# md_ver10_4.net
KiCad netlist of a schematic drawn in EAGLE
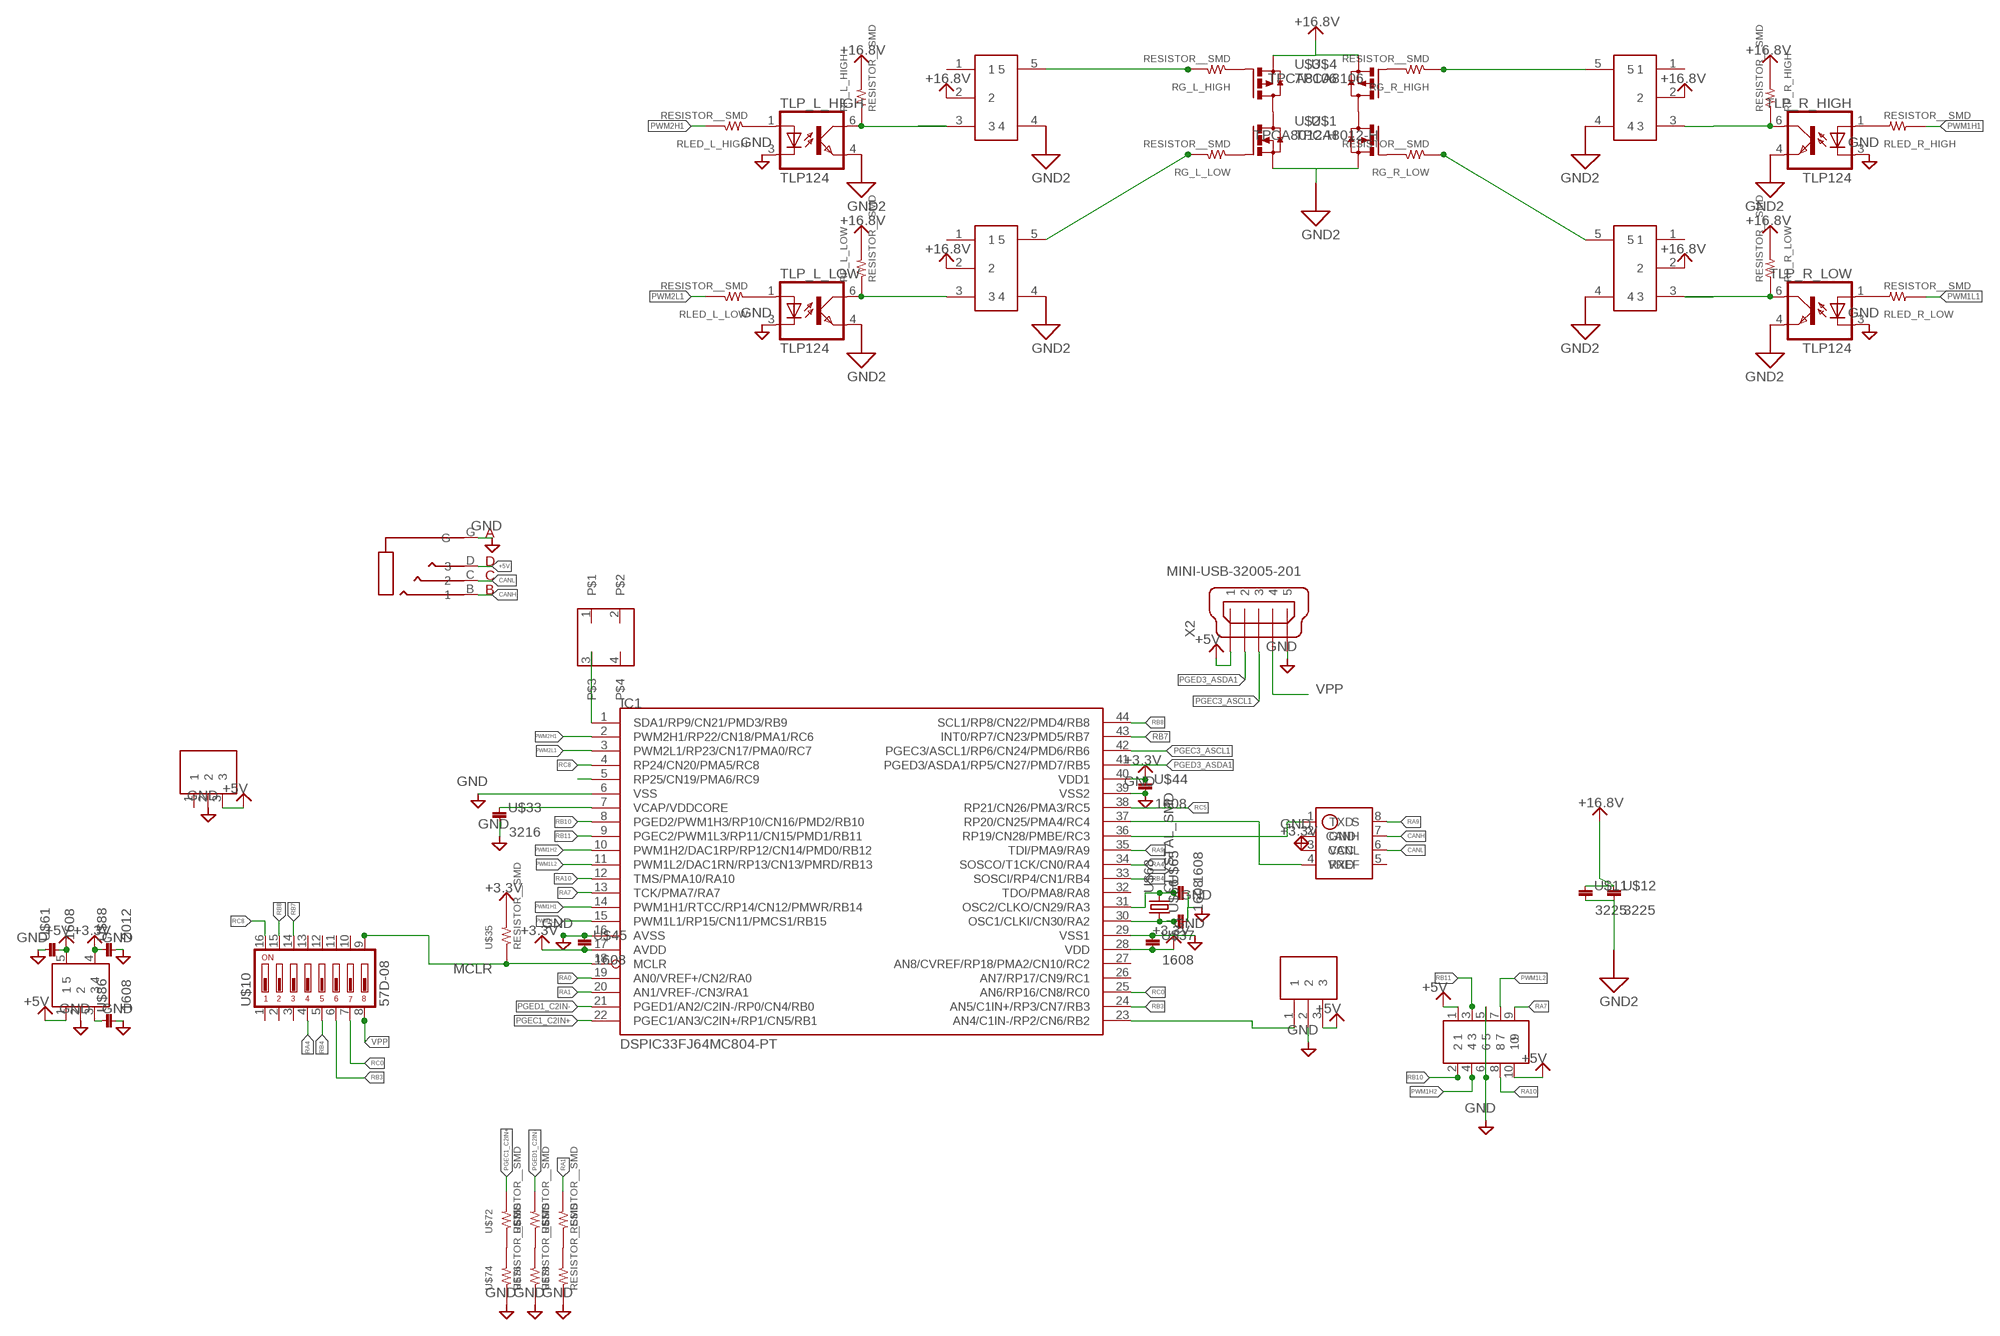
[diagram p0: schematic, sheet 1]

(export (version "E")
  (design (tool "Eeschema 10.0.6"))
  (components
    (comp (ref "IC1")
      (value "DSPIC33FJ64MC804-PT")
      (footprint "eagle-import:TQFP44")
      (libsource (lib "eagle-import") (part "DSPIC33FJ64MC804-PT"))
    )
    (comp (ref "IC_L_HIGH")
      (value "MCP1415")
      (footprint "eagle-import:SOT23-5L")
      (libsource (lib "eagle-import") (part "MCP1415"))
    )
    (comp (ref "IC_L_LOW")
      (value "MCP1415")
      (footprint "eagle-import:SOT23-5L")
      (libsource (lib "eagle-import") (part "MCP1415"))
    )
    (comp (ref "IC_R_HIGH")
      (value "MCP1415")
      (footprint "eagle-import:SOT23-5L")
      (libsource (lib "eagle-import") (part "MCP1415"))
    )
    (comp (ref "IC_R_LOW")
      (value "MCP1415")
      (footprint "eagle-import:SOT23-5L")
      (libsource (lib "eagle-import") (part "MCP1415"))
    )
    (comp (ref "RG_L_HIGH")
      (value "RESISTOR__SMD")
      (footprint "eagle-import:1608")
      (libsource (lib "eagle-import") (part "RESISTOR__SMD"))
    )
    (comp (ref "RG_L_LOW")
      (value "RESISTOR__SMD")
      (footprint "eagle-import:1608")
      (libsource (lib "eagle-import") (part "RESISTOR__SMD"))
    )
    (comp (ref "RG_R_HIGH")
      (value "RESISTOR__SMD")
      (footprint "eagle-import:1608")
      (libsource (lib "eagle-import") (part "RESISTOR__SMD"))
    )
    (comp (ref "RG_R_LOW")
      (value "RESISTOR__SMD")
      (footprint "eagle-import:1608")
      (libsource (lib "eagle-import") (part "RESISTOR__SMD"))
    )
    (comp (ref "RLED_L_HIGH")
      (value "RESISTOR__SMD")
      (footprint "eagle-import:1608")
      (libsource (lib "eagle-import") (part "RESISTOR__SMD"))
    )
    (comp (ref "RLED_L_LOW")
      (value "RESISTOR__SMD")
      (footprint "eagle-import:1608")
      (libsource (lib "eagle-import") (part "RESISTOR__SMD"))
    )
    (comp (ref "RLED_R_HIGH")
      (value "RESISTOR__SMD")
      (footprint "eagle-import:1608")
      (libsource (lib "eagle-import") (part "RESISTOR__SMD"))
    )
    (comp (ref "RLED_R_LOW")
      (value "RESISTOR__SMD")
      (footprint "eagle-import:1608")
      (libsource (lib "eagle-import") (part "RESISTOR__SMD"))
    )
    (comp (ref "RP_L_HIGH")
      (value "RESISTOR__SMD")
      (footprint "eagle-import:1608")
      (libsource (lib "eagle-import") (part "RESISTOR__SMD"))
    )
    (comp (ref "RP_L_LOW")
      (value "RESISTOR__SMD")
      (footprint "eagle-import:1608")
      (libsource (lib "eagle-import") (part "RESISTOR__SMD"))
    )
    (comp (ref "RP_R_HIGH")
      (value "RESISTOR__SMD")
      (footprint "eagle-import:1608")
      (libsource (lib "eagle-import") (part "RESISTOR__SMD"))
    )
    (comp (ref "RP_R_LOW")
      (value "RESISTOR__SMD")
      (footprint "eagle-import:1608")
      (libsource (lib "eagle-import") (part "RESISTOR__SMD"))
    )
    (comp (ref "TLP_L_HIGH")
      (value "TLP124")
      (footprint "eagle-import:11−4C1")
      (libsource (lib "eagle-import") (part "TLP124"))
    )
    (comp (ref "TLP_L_LOW")
      (value "TLP124")
      (footprint "eagle-import:11−4C1")
      (libsource (lib "eagle-import") (part "TLP124"))
    )
    (comp (ref "TLP_R_HIGH")
      (value "TLP124")
      (footprint "eagle-import:11−4C1")
      (libsource (lib "eagle-import") (part "TLP124"))
    )
    (comp (ref "TLP_R_LOW")
      (value "TLP124")
      (footprint "eagle-import:11−4C1")
      (libsource (lib "eagle-import") (part "TLP124"))
    )
    (comp (ref "U$1")
      (value "TPCA8012-H")
      (footprint "eagle-import:2-5Q1A")
      (libsource (lib "eagle-import") (part "TPCA8012-H"))
    )
    (comp (ref "U$2")
      (value "TPCA8012-H")
      (footprint "eagle-import:2-5Q1A")
      (libsource (lib "eagle-import") (part "TPCA8012-H"))
    )
    (comp (ref "U$3")
      (value "TPCA8106")
      (footprint "eagle-import:2-5Q1A")
      (libsource (lib "eagle-import") (part "TPCA8106"))
    )
    (comp (ref "U$4")
      (value "TPCA8106")
      (footprint "eagle-import:2-5Q1A")
      (libsource (lib "eagle-import") (part "TPCA8106"))
    )
    (comp (ref "U$7")
      (value "ＰＬ－ＩＲＭ")
      (footprint "eagle-import:ＰＬ－ＩＲＭ")
      (libsource (lib "eagle-import") (part "ＰＬ－ＩＲＭ"))
    )
    (comp (ref "U$8")
      (value "Ｒ－７８Ｅ５．０")
      (footprint "eagle-import:Ｒ－７８Ｅ５．０")
      (libsource (lib "eagle-import") (part "Ｒ－７８Ｅ５．０"))
    )
    (comp (ref "U$9")
      (value "TAR5SB")
      (footprint "eagle-import:SSOP5-P-0.95")
      (libsource (lib "eagle-import") (part "TAR5SB"))
    )
    (comp (ref "U$10")
      (value "57D-08")
      (footprint "eagle-import:57D")
      (libsource (lib "eagle-import") (part "57D-08"))
    )
    (comp (ref "U$11")
      (value "3225")
      (footprint "eagle-import:3225")
      (libsource (lib "eagle-import") (part "3225"))
    )
    (comp (ref "U$12")
      (value "3225")
      (footprint "eagle-import:3225")
      (libsource (lib "eagle-import") (part "3225"))
    )
    (comp (ref "U$15")
      (value "PIN_HEADER_52")
      (footprint "eagle-import:PIN_HEADER_5_2")
      (libsource (lib "eagle-import") (part "PIN_HEADER_52"))
    )
    (comp (ref "U$33")
      (value "3216")
      (footprint "eagle-import:3216")
      (libsource (lib "eagle-import") (part "3216"))
    )
    (comp (ref "U$35")
      (value "RESISTOR__SMD")
      (footprint "eagle-import:1608")
      (libsource (lib "eagle-import") (part "RESISTOR__SMD"))
    )
    (comp (ref "U$37")
      (value "1608")
      (footprint "eagle-import:1608")
      (libsource (lib "eagle-import") (part "1608"))
    )
    (comp (ref "U$44")
      (value "1608")
      (footprint "eagle-import:1608")
      (libsource (lib "eagle-import") (part "1608"))
    )
    (comp (ref "U$45")
      (value "1608")
      (footprint "eagle-import:1608")
      (libsource (lib "eagle-import") (part "1608"))
    )
    (comp (ref "U$61")
      (value "1608")
      (footprint "eagle-import:1608")
      (libsource (lib "eagle-import") (part "1608"))
    )
    (comp (ref "U$64")
      (value "AUDIO4")
      (footprint "eagle-import:AUDIO4_MJ")
      (libsource (lib "eagle-import") (part "AUDIO4"))
    )
    (comp (ref "U$65")
      (value "1608")
      (footprint "eagle-import:1608")
      (libsource (lib "eagle-import") (part "1608"))
    )
    (comp (ref "U$66")
      (value "1608")
      (footprint "eagle-import:1608")
      (libsource (lib "eagle-import") (part "1608"))
    )
    (comp (ref "U$68")
      (value "CLYSTAL_SMD")
      (footprint "eagle-import:CRYSTAL_SMD")
      (libsource (lib "eagle-import") (part "CLYSTAL_SMD"))
    )
    (comp (ref "U$69")
      (value "TACT")
      (footprint "eagle-import:TL1105")
      (libsource (lib "eagle-import") (part "TACT"))
    )
    (comp (ref "U$72")
      (value "RESISTOR__SMD")
      (footprint "eagle-import:1608")
      (libsource (lib "eagle-import") (part "RESISTOR__SMD"))
    )
    (comp (ref "U$74")
      (value "RESISTOR__SMD")
      (footprint "eagle-import:1608")
      (libsource (lib "eagle-import") (part "RESISTOR__SMD"))
    )
    (comp (ref "U$75")
      (value "RESISTOR__SMD")
      (footprint "eagle-import:1608")
      (libsource (lib "eagle-import") (part "RESISTOR__SMD"))
    )
    (comp (ref "U$76")
      (value "RESISTOR__SMD")
      (footprint "eagle-import:1608")
      (libsource (lib "eagle-import") (part "RESISTOR__SMD"))
    )
    (comp (ref "U$77")
      (value "RESISTOR__SMD")
      (footprint "eagle-import:1608")
      (libsource (lib "eagle-import") (part "RESISTOR__SMD"))
    )
    (comp (ref "U$78")
      (value "RESISTOR__SMD")
      (footprint "eagle-import:1608")
      (libsource (lib "eagle-import") (part "RESISTOR__SMD"))
    )
    (comp (ref "U$82")
      (value "SN65HVD1050")
      (footprint "eagle-import:SOIC8")
      (libsource (lib "eagle-import") (part "SN65HVD1050"))
    )
    (comp (ref "U$86")
      (value "1608")
      (footprint "eagle-import:1608")
      (libsource (lib "eagle-import") (part "1608"))
    )
    (comp (ref "U$88")
      (value "2012")
      (footprint "eagle-import:2012")
      (libsource (lib "eagle-import") (part "2012"))
    )
    (comp (ref "X2")
      (value "MINI-USB-32005-201")
      (footprint "eagle-import:32005-201")
      (libsource (lib "eagle-import") (part "MINI-USB-32005-201"))
    )
  )
  (nets
    (net (code "1") (name "+3.3V") (class "Default")
      (node (ref "IC1") (pin "17") (pinfunction "AVDD_17") (pintype "power_in"))
      (node (ref "IC1") (pin "28") (pinfunction "VDD_28") (pintype "power_in"))
      (node (ref "IC1") (pin "40") (pinfunction "VDD1_40") (pintype "power_in"))
      (node (ref "U$35") (pin "2") (pinfunction "P$2_2") (pintype "passive"))
      (node (ref "U$37") (pin "P$2") (pinfunction "2_P$2") (pintype "passive"))
      (node (ref "U$44") (pin "P$1") (pinfunction "1_P$1") (pintype "passive"))
      (node (ref "U$45") (pin "P$2") (pinfunction "2_P$2") (pintype "passive"))
      (node (ref "U$82") (pin "3") (pinfunction "VCC_3") (pintype "bidirectional"))
      (node (ref "U$88") (pin "1") (pinfunction "1_1") (pintype "passive"))
      (node (ref "U$9") (pin "4") (pinfunction "4_4") (pintype "bidirectional"))
    )
    (net (code "2") (name "+5V") (class "Default")
      (node (ref "U$15") (pin "1") (pinfunction "1_1") (pintype "bidirectional"))
      (node (ref "U$15") (pin "10") (pinfunction "10_10") (pintype "bidirectional"))
      (node (ref "U$61") (pin "P$2") (pinfunction "2_P$2") (pintype "passive"))
      (node (ref "U$64") (pin "D") (pinfunction "3_D") (pintype "bidirectional"))
      (node (ref "U$7") (pin "3") (pinfunction "3_3") (pintype "bidirectional"))
      (node (ref "U$8") (pin "3") (pinfunction "3_3") (pintype "bidirectional"))
      (node (ref "U$9") (pin "1") (pinfunction "1_1") (pintype "bidirectional"))
      (node (ref "U$9") (pin "5") (pinfunction "5_5") (pintype "bidirectional"))
      (node (ref "X2") (pin "1") (pinfunction "1_1") (pintype "passive"))
    )
    (net (code "3") (name "+16.8V") (class "Default")
      (node (ref "IC_L_HIGH") (pin "2") (pinfunction "2_2") (pintype "bidirectional"))
      (node (ref "IC_L_LOW") (pin "2") (pinfunction "2_2") (pintype "bidirectional"))
      (node (ref "IC_R_HIGH") (pin "2") (pinfunction "2_2") (pintype "bidirectional"))
      (node (ref "IC_R_LOW") (pin "2") (pinfunction "2_2") (pintype "bidirectional"))
      (node (ref "RP_L_HIGH") (pin "2") (pinfunction "P$2_2") (pintype "passive"))
      (node (ref "RP_L_LOW") (pin "2") (pinfunction "P$2_2") (pintype "passive"))
      (node (ref "RP_R_HIGH") (pin "2") (pinfunction "P$2_2") (pintype "passive"))
      (node (ref "RP_R_LOW") (pin "2") (pinfunction "P$2_2") (pintype "passive"))
      (node (ref "U$11") (pin "P$1") (pinfunction "1_P$1") (pintype "passive"))
      (node (ref "U$12") (pin "P$1") (pinfunction "1_P$1") (pintype "passive"))
      (node (ref "U$3") (pin "1") (pinfunction "S_1") (pintype "passive"))
      (node (ref "U$3") (pin "2") (pinfunction "S_2") (pintype "passive"))
      (node (ref "U$3") (pin "3") (pinfunction "S_3") (pintype "passive"))
      (node (ref "U$4") (pin "1") (pinfunction "S_1") (pintype "passive"))
      (node (ref "U$4") (pin "2") (pinfunction "S_2") (pintype "passive"))
      (node (ref "U$4") (pin "3") (pinfunction "S_3") (pintype "passive"))
    )
    (net (code "4") (name "/MCLR") (class "Default")
      (node (ref "IC1") (pin "18") (pinfunction "MCLR_18") (pintype "input"))
      (node (ref "U$10") (pin "9") (pinfunction "9_9") (pintype "passive"))
      (node (ref "U$35") (pin "1") (pinfunction "P$1_1") (pintype "passive"))
    )
    (net (code "5") (name "CANH") (class "Default")
      (node (ref "U$64") (pin "B") (pinfunction "1_B") (pintype "bidirectional"))
      (node (ref "U$82") (pin "7") (pinfunction "CANH_7") (pintype "bidirectional"))
    )
    (net (code "6") (name "CANL") (class "Default")
      (node (ref "U$64") (pin "C") (pinfunction "2_C") (pintype "bidirectional"))
      (node (ref "U$82") (pin "6") (pinfunction "CANL_6") (pintype "bidirectional"))
    )
    (net (code "7") (name "GND") (class "Default")
      (node (ref "IC1") (pin "16") (pinfunction "AVSS_16") (pintype "power_in"))
      (node (ref "IC1") (pin "29") (pinfunction "VSS1_29") (pintype "power_in"))
      (node (ref "IC1") (pin "39") (pinfunction "VSS2_39") (pintype "power_in"))
      (node (ref "IC1") (pin "6") (pinfunction "VSS_6") (pintype "power_in"))
      (node (ref "TLP_L_HIGH") (pin "3") (pinfunction "C_3") (pintype "passive"))
      (node (ref "TLP_L_LOW") (pin "3") (pinfunction "C_3") (pintype "passive"))
      (node (ref "TLP_R_HIGH") (pin "3") (pinfunction "C_3") (pintype "passive"))
      (node (ref "TLP_R_LOW") (pin "3") (pinfunction "C_3") (pintype "passive"))
      (node (ref "U$15") (pin "5") (pinfunction "5_5") (pintype "bidirectional"))
      (node (ref "U$15") (pin "6") (pinfunction "6_6") (pintype "bidirectional"))
      (node (ref "U$33") (pin "P$2") (pinfunction "2_P$2") (pintype "passive"))
      (node (ref "U$37") (pin "P$1") (pinfunction "1_P$1") (pintype "passive"))
      (node (ref "U$44") (pin "P$2") (pinfunction "2_P$2") (pintype "passive"))
      (node (ref "U$45") (pin "P$1") (pinfunction "1_P$1") (pintype "passive"))
      (node (ref "U$61") (pin "P$1") (pinfunction "1_P$1") (pintype "passive"))
      (node (ref "U$64") (pin "G") (pinfunction "G_G") (pintype "bidirectional"))
      (node (ref "U$65") (pin "P$2") (pinfunction "2_P$2") (pintype "passive"))
      (node (ref "U$66") (pin "P$2") (pinfunction "2_P$2") (pintype "passive"))
      (node (ref "U$7") (pin "2") (pinfunction "2_2") (pintype "bidirectional"))
      (node (ref "U$74") (pin "1") (pinfunction "P$1_1") (pintype "passive"))
      (node (ref "U$76") (pin "1") (pinfunction "P$1_1") (pintype "passive"))
      (node (ref "U$78") (pin "1") (pinfunction "P$1_1") (pintype "passive"))
      (node (ref "U$8") (pin "2") (pinfunction "2_2") (pintype "bidirectional"))
      (node (ref "U$82") (pin "2") (pinfunction "GND_2") (pintype "bidirectional"))
      (node (ref "U$86") (pin "P$2") (pinfunction "2_P$2") (pintype "passive"))
      (node (ref "U$88") (pin "2") (pinfunction "2_2") (pintype "passive"))
      (node (ref "U$9") (pin "2") (pinfunction "2_2") (pintype "bidirectional"))
      (node (ref "X2") (pin "5") (pinfunction "5_5") (pintype "passive"))
    )
    (net (code "8") (name "GND2") (class "Default")
      (node (ref "IC_L_HIGH") (pin "4") (pinfunction "4_4") (pintype "bidirectional"))
      (node (ref "IC_L_LOW") (pin "4") (pinfunction "4_4") (pintype "bidirectional"))
      (node (ref "IC_R_HIGH") (pin "4") (pinfunction "4_4") (pintype "bidirectional"))
      (node (ref "IC_R_LOW") (pin "4") (pinfunction "4_4") (pintype "bidirectional"))
      (node (ref "TLP_L_HIGH") (pin "4") (pinfunction "EMIT_4") (pintype "passive"))
      (node (ref "TLP_L_LOW") (pin "4") (pinfunction "EMIT_4") (pintype "passive"))
      (node (ref "TLP_R_HIGH") (pin "4") (pinfunction "EMIT_4") (pintype "passive"))
      (node (ref "TLP_R_LOW") (pin "4") (pinfunction "EMIT_4") (pintype "passive"))
      (node (ref "U$1") (pin "1") (pinfunction "S_1") (pintype "passive"))
      (node (ref "U$1") (pin "2") (pinfunction "S_2") (pintype "passive"))
      (node (ref "U$1") (pin "3") (pinfunction "S_3") (pintype "passive"))
      (node (ref "U$11") (pin "P$2") (pinfunction "2_P$2") (pintype "passive"))
      (node (ref "U$12") (pin "P$2") (pinfunction "2_P$2") (pintype "passive"))
      (node (ref "U$2") (pin "1") (pinfunction "S_1") (pintype "passive"))
      (node (ref "U$2") (pin "2") (pinfunction "S_2") (pintype "passive"))
      (node (ref "U$2") (pin "3") (pinfunction "S_3") (pintype "passive"))
    )
    (net (code "9") (name "Net-(IC1-AN4{slash}C1IN-{slash}RP2{slash}CN6{slash}RB2)") (class "Default")
      (node (ref "IC1") (pin "23") (pinfunction "AN4/C1IN-/RP2/CN6/RB2_23") (pintype "bidirectional"))
      (node (ref "U$7") (pin "1") (pinfunction "1_1") (pintype "bidirectional"))
    )
    (net (code "10") (name "Net-(IC1-OSC1{slash}CLKI{slash}CN30{slash}RA2)") (class "Default")
      (node (ref "IC1") (pin "30") (pinfunction "OSC1/CLKI/CN30/RA2_30") (pintype "bidirectional"))
      (node (ref "U$66") (pin "P$1") (pinfunction "1_P$1") (pintype "passive"))
      (node (ref "U$68") (pin "1") (pinfunction "1_1") (pintype "passive"))
    )
    (net (code "11") (name "Net-(IC1-OSC2{slash}CLKO{slash}CN29{slash}RA3)") (class "Default")
      (node (ref "IC1") (pin "31") (pinfunction "OSC2/CLKO/CN29/RA3_31") (pintype "bidirectional"))
      (node (ref "U$65") (pin "P$1") (pinfunction "1_P$1") (pintype "passive"))
      (node (ref "U$68") (pin "2") (pinfunction "2_2") (pintype "passive"))
    )
    (net (code "12") (name "Net-(IC1-RP19{slash}CN28{slash}PMBE{slash}RC3)") (class "Default")
      (node (ref "IC1") (pin "36") (pinfunction "RP19/CN28/PMBE/RC3_36") (pintype "bidirectional"))
      (node (ref "U$82") (pin "1") (pinfunction "TXD_1") (pintype "bidirectional"))
    )
    (net (code "13") (name "Net-(IC1-RP20{slash}CN25{slash}PMA4{slash}RC4)") (class "Default")
      (node (ref "IC1") (pin "37") (pinfunction "RP20/CN25/PMA4/RC4_37") (pintype "bidirectional"))
      (node (ref "U$82") (pin "4") (pinfunction "RXD_4") (pintype "bidirectional"))
    )
    (net (code "14") (name "Net-(IC1-SDA1{slash}RP9{slash}CN21{slash}PMD3{slash}RB9)") (class "Default")
      (node (ref "IC1") (pin "1") (pinfunction "SDA1/RP9/CN21/PMD3/RB9_1") (pintype "bidirectional"))
      (node (ref "U$69") (pin "3") (pinfunction "P$3_3") (pintype "bidirectional"))
    )
    (net (code "15") (name "Net-(IC1-VCAP{slash}VDDCORE)") (class "Default")
      (node (ref "IC1") (pin "7") (pinfunction "VCAP/VDDCORE_7") (pintype "power_in"))
      (node (ref "U$33") (pin "P$1") (pinfunction "1_P$1") (pintype "passive"))
    )
    (net (code "16") (name "Net-(RG_L_HIGH-P$1)") (class "Default")
      (node (ref "RG_L_HIGH") (pin "1") (pinfunction "P$1_1") (pintype "passive"))
      (node (ref "U$3") (pin "4") (pinfunction "G_4") (pintype "passive"))
    )
    (net (code "17") (name "Net-(RG_L_HIGH-P$2)") (class "Default")
      (node (ref "IC_L_HIGH") (pin "5") (pinfunction "5_5") (pintype "bidirectional"))
      (node (ref "RG_L_HIGH") (pin "2") (pinfunction "P$2_2") (pintype "passive"))
    )
    (net (code "18") (name "Net-(RG_L_LOW-P$1)") (class "Default")
      (node (ref "RG_L_LOW") (pin "1") (pinfunction "P$1_1") (pintype "passive"))
      (node (ref "U$2") (pin "4") (pinfunction "G_4") (pintype "passive"))
    )
    (net (code "19") (name "Net-(RG_L_LOW-P$2)") (class "Default")
      (node (ref "IC_L_LOW") (pin "5") (pinfunction "5_5") (pintype "bidirectional"))
      (node (ref "RG_L_LOW") (pin "2") (pinfunction "P$2_2") (pintype "passive"))
    )
    (net (code "20") (name "Net-(RG_R_HIGH-P$1)") (class "Default")
      (node (ref "IC_R_HIGH") (pin "5") (pinfunction "5_5") (pintype "bidirectional"))
      (node (ref "RG_R_HIGH") (pin "1") (pinfunction "P$1_1") (pintype "passive"))
    )
    (net (code "21") (name "Net-(RG_R_HIGH-P$2)") (class "Default")
      (node (ref "RG_R_HIGH") (pin "2") (pinfunction "P$2_2") (pintype "passive"))
      (node (ref "U$4") (pin "4") (pinfunction "G_4") (pintype "passive"))
    )
    (net (code "22") (name "Net-(RG_R_LOW-P$1)") (class "Default")
      (node (ref "IC_R_LOW") (pin "5") (pinfunction "5_5") (pintype "bidirectional"))
      (node (ref "RG_R_LOW") (pin "1") (pinfunction "P$1_1") (pintype "passive"))
    )
    (net (code "23") (name "Net-(RG_R_LOW-P$2)") (class "Default")
      (node (ref "RG_R_LOW") (pin "2") (pinfunction "P$2_2") (pintype "passive"))
      (node (ref "U$1") (pin "4") (pinfunction "G_4") (pintype "passive"))
    )
    (net (code "24") (name "Net-(RLED_L_HIGH-P$1)") (class "Default")
      (node (ref "RLED_L_HIGH") (pin "1") (pinfunction "P$1_1") (pintype "passive"))
      (node (ref "TLP_L_HIGH") (pin "1") (pinfunction "A_1") (pintype "passive"))
    )
    (net (code "25") (name "Net-(RLED_L_LOW-P$1)") (class "Default")
      (node (ref "RLED_L_LOW") (pin "1") (pinfunction "P$1_1") (pintype "passive"))
      (node (ref "TLP_L_LOW") (pin "1") (pinfunction "A_1") (pintype "passive"))
    )
    (net (code "26") (name "Net-(RLED_R_HIGH-P$1)") (class "Default")
      (node (ref "RLED_R_HIGH") (pin "1") (pinfunction "P$1_1") (pintype "passive"))
      (node (ref "TLP_R_HIGH") (pin "1") (pinfunction "A_1") (pintype "passive"))
    )
    (net (code "27") (name "Net-(RLED_R_LOW-P$1)") (class "Default")
      (node (ref "RLED_R_LOW") (pin "1") (pinfunction "P$1_1") (pintype "passive"))
      (node (ref "TLP_R_LOW") (pin "1") (pinfunction "A_1") (pintype "passive"))
    )
    (net (code "28") (name "Net-(RP_L_HIGH-P$1)") (class "Default")
      (node (ref "IC_L_HIGH") (pin "3") (pinfunction "3_3") (pintype "bidirectional"))
      (node (ref "RP_L_HIGH") (pin "1") (pinfunction "P$1_1") (pintype "passive"))
      (node (ref "TLP_L_HIGH") (pin "6") (pinfunction "COL_6") (pintype "passive"))
    )
    (net (code "29") (name "Net-(RP_L_LOW-P$1)") (class "Default")
      (node (ref "IC_L_LOW") (pin "3") (pinfunction "3_3") (pintype "bidirectional"))
      (node (ref "RP_L_LOW") (pin "1") (pinfunction "P$1_1") (pintype "passive"))
      (node (ref "TLP_L_LOW") (pin "6") (pinfunction "COL_6") (pintype "passive"))
    )
    (net (code "30") (name "Net-(RP_R_HIGH-P$1)") (class "Default")
      (node (ref "IC_R_HIGH") (pin "3") (pinfunction "3_3") (pintype "bidirectional"))
      (node (ref "RP_R_HIGH") (pin "1") (pinfunction "P$1_1") (pintype "passive"))
      (node (ref "TLP_R_HIGH") (pin "6") (pinfunction "COL_6") (pintype "passive"))
    )
    (net (code "31") (name "Net-(RP_R_LOW-P$1)") (class "Default")
      (node (ref "IC_R_LOW") (pin "3") (pinfunction "3_3") (pintype "bidirectional"))
      (node (ref "RP_R_LOW") (pin "1") (pinfunction "P$1_1") (pintype "passive"))
      (node (ref "TLP_R_LOW") (pin "6") (pinfunction "COL_6") (pintype "passive"))
    )
    (net (code "32") (name "Net-(U$1-D-Pad5)") (class "Default")
      (node (ref "U$1") (pin "5") (pinfunction "D_5") (pintype "passive"))
      (node (ref "U$1") (pin "6") (pinfunction "D_6") (pintype "passive"))
      (node (ref "U$1") (pin "7") (pinfunction "D_7") (pintype "passive"))
      (node (ref "U$1") (pin "8") (pinfunction "D_8") (pintype "passive"))
      (node (ref "U$4") (pin "5") (pinfunction "D_5") (pintype "passive"))
      (node (ref "U$4") (pin "6") (pinfunction "D_6") (pintype "passive"))
      (node (ref "U$4") (pin "7") (pinfunction "D_7") (pintype "passive"))
      (node (ref "U$4") (pin "8") (pinfunction "D_8") (pintype "passive"))
    )
    (net (code "33") (name "Net-(U$2-D-Pad5)") (class "Default")
      (node (ref "U$2") (pin "5") (pinfunction "D_5") (pintype "passive"))
      (node (ref "U$2") (pin "6") (pinfunction "D_6") (pintype "passive"))
      (node (ref "U$2") (pin "7") (pinfunction "D_7") (pintype "passive"))
      (node (ref "U$2") (pin "8") (pinfunction "D_8") (pintype "passive"))
      (node (ref "U$3") (pin "5") (pinfunction "D_5") (pintype "passive"))
      (node (ref "U$3") (pin "6") (pinfunction "D_6") (pintype "passive"))
      (node (ref "U$3") (pin "7") (pinfunction "D_7") (pintype "passive"))
      (node (ref "U$3") (pin "8") (pinfunction "D_8") (pintype "passive"))
    )
    (net (code "34") (name "Net-(U$72-P$1)") (class "Default")
      (node (ref "U$72") (pin "1") (pinfunction "P$1_1") (pintype "passive"))
      (node (ref "U$74") (pin "2") (pinfunction "P$2_2") (pintype "passive"))
    )
    (net (code "35") (name "Net-(U$75-P$1)") (class "Default")
      (node (ref "U$75") (pin "1") (pinfunction "P$1_1") (pintype "passive"))
      (node (ref "U$76") (pin "2") (pinfunction "P$2_2") (pintype "passive"))
    )
    (net (code "36") (name "Net-(U$77-P$1)") (class "Default")
      (node (ref "U$77") (pin "1") (pinfunction "P$1_1") (pintype "passive"))
      (node (ref "U$78") (pin "2") (pinfunction "P$2_2") (pintype "passive"))
    )
    (net (code "37") (name "Net-(U$86-1)") (class "Default")
      (node (ref "U$86") (pin "P$1") (pinfunction "1_P$1") (pintype "passive"))
      (node (ref "U$9") (pin "3") (pinfunction "3_3") (pintype "bidirectional"))
    )
    (net (code "38") (name "PGEC1_C2IN+") (class "Default")
      (node (ref "IC1") (pin "22") (pinfunction "PGEC1/AN3/C2IN+/RP1/CN5/RB1_22") (pintype "bidirectional"))
      (node (ref "U$72") (pin "2") (pinfunction "P$2_2") (pintype "passive"))
    )
    (net (code "39") (name "PGEC3_ASCL1") (class "Default")
      (node (ref "IC1") (pin "42") (pinfunction "PGEC3/ASCL1/RP6/CN24/PMD6/RB6_42") (pintype "bidirectional"))
      (node (ref "X2") (pin "3") (pinfunction "3_3") (pintype "passive"))
    )
    (net (code "40") (name "PGED1_C2IN-") (class "Default")
      (node (ref "IC1") (pin "21") (pinfunction "PGED1/AN2/C2IN-/RP0/CN4/RB0_21") (pintype "bidirectional"))
      (node (ref "U$75") (pin "2") (pinfunction "P$2_2") (pintype "passive"))
    )
    (net (code "41") (name "PGED3_ASDA1") (class "Default")
      (node (ref "IC1") (pin "41") (pinfunction "PGED3/ASDA1/RP5/CN27/PMD7/RB5_41") (pintype "bidirectional"))
      (node (ref "X2") (pin "2") (pinfunction "2_2") (pintype "passive"))
    )
    (net (code "42") (name "PWM1H1") (class "Default")
      (node (ref "IC1") (pin "14") (pinfunction "PWM1H1/RTCC/RP14/CN12/PMWR/RB14_14") (pintype "bidirectional"))
      (node (ref "RLED_R_HIGH") (pin "2") (pinfunction "P$2_2") (pintype "passive"))
    )
    (net (code "43") (name "PWM1H2") (class "Default")
      (node (ref "IC1") (pin "10") (pinfunction "PWM1H2/DAC1RP/RP12/CN14/PMD0/RB12_10") (pintype "bidirectional"))
      (node (ref "U$15") (pin "4") (pinfunction "4_4") (pintype "bidirectional"))
    )
    (net (code "44") (name "PWM1L1") (class "Default")
      (node (ref "IC1") (pin "15") (pinfunction "PWM1L1/RP15/CN11/PMCS1/RB15_15") (pintype "bidirectional"))
      (node (ref "RLED_R_LOW") (pin "2") (pinfunction "P$2_2") (pintype "passive"))
    )
    (net (code "45") (name "PWM1L2") (class "Default")
      (node (ref "IC1") (pin "11") (pinfunction "PWM1L2/DAC1RN/RP13/CN13/PMRD/RB13_11") (pintype "bidirectional"))
      (node (ref "U$15") (pin "7") (pinfunction "7_7") (pintype "bidirectional"))
    )
    (net (code "46") (name "PWM2H1") (class "Default")
      (node (ref "IC1") (pin "2") (pinfunction "PWM2H1/RP22/CN18/PMA1/RC6_2") (pintype "bidirectional"))
      (node (ref "RLED_L_HIGH") (pin "2") (pinfunction "P$2_2") (pintype "passive"))
    )
    (net (code "47") (name "PWM2L1") (class "Default")
      (node (ref "IC1") (pin "3") (pinfunction "PWM2L1/RP23/CN17/PMA0/RC7_3") (pintype "bidirectional"))
      (node (ref "RLED_L_LOW") (pin "2") (pinfunction "P$2_2") (pintype "passive"))
    )
    (net (code "48") (name "RA0") (class "Default")
      (node (ref "IC1") (pin "19") (pinfunction "AN0/VREF+/CN2/RA0_19") (pintype "bidirectional"))
    )
    (net (code "49") (name "RA1") (class "Default")
      (node (ref "IC1") (pin "20") (pinfunction "AN1/VREF-/CN3/RA1_20") (pintype "bidirectional"))
      (node (ref "U$77") (pin "2") (pinfunction "P$2_2") (pintype "passive"))
    )
    (net (code "50") (name "RA4") (class "Default")
      (node (ref "IC1") (pin "34") (pinfunction "SOSCO/T1CK/CN0/RA4_34") (pintype "bidirectional"))
      (node (ref "U$10") (pin "4") (pinfunction "4_4") (pintype "passive"))
    )
    (net (code "51") (name "RA7") (class "Default")
      (node (ref "IC1") (pin "13") (pinfunction "TCK/PMA7/RA7_13") (pintype "bidirectional"))
      (node (ref "U$15") (pin "9") (pinfunction "9_9") (pintype "bidirectional"))
    )
    (net (code "52") (name "RA9") (class "Default")
      (node (ref "IC1") (pin "35") (pinfunction "TDI/PMA9/RA9_35") (pintype "bidirectional"))
      (node (ref "U$82") (pin "8") (pinfunction "S_8") (pintype "bidirectional"))
    )
    (net (code "53") (name "RA10") (class "Default")
      (node (ref "IC1") (pin "12") (pinfunction "TMS/PMA10/RA10_12") (pintype "bidirectional"))
      (node (ref "U$15") (pin "8") (pinfunction "8_8") (pintype "bidirectional"))
    )
    (net (code "54") (name "RB3") (class "Default")
      (node (ref "IC1") (pin "24") (pinfunction "AN5/C1IN+/RP3/CN7/RB3_24") (pintype "bidirectional"))
      (node (ref "U$10") (pin "6") (pinfunction "6_6") (pintype "passive"))
    )
    (net (code "55") (name "RB4") (class "Default")
      (node (ref "IC1") (pin "33") (pinfunction "SOSCI/RP4/CN1/RB4_33") (pintype "bidirectional"))
      (node (ref "U$10") (pin "5") (pinfunction "5_5") (pintype "passive"))
    )
    (net (code "56") (name "RB7") (class "Default")
      (node (ref "IC1") (pin "43") (pinfunction "INT0/RP7/CN23/PMD5/RB7_43") (pintype "bidirectional"))
      (node (ref "U$10") (pin "14") (pinfunction "14_14") (pintype "passive"))
    )
    (net (code "57") (name "RB8") (class "Default")
      (node (ref "IC1") (pin "44") (pinfunction "SCL1/RP8/CN22/PMD4/RB8_44") (pintype "bidirectional"))
      (node (ref "U$10") (pin "15") (pinfunction "15_15") (pintype "passive"))
    )
    (net (code "58") (name "RB10") (class "Default")
      (node (ref "IC1") (pin "8") (pinfunction "PGED2/PWM1H3/RP10/CN16/PMD2/RB10_8") (pintype "bidirectional"))
      (node (ref "U$15") (pin "2") (pinfunction "2_2") (pintype "bidirectional"))
    )
    (net (code "59") (name "RB11") (class "Default")
      (node (ref "IC1") (pin "9") (pinfunction "PGEC2/PWM1L3/RP11/CN15/PMD1/RB11_9") (pintype "bidirectional"))
      (node (ref "U$15") (pin "3") (pinfunction "3_3") (pintype "bidirectional"))
    )
    (net (code "60") (name "RC0") (class "Default")
      (node (ref "IC1") (pin "25") (pinfunction "AN6/RP16/CN8/RC0_25") (pintype "bidirectional"))
      (node (ref "U$10") (pin "7") (pinfunction "7_7") (pintype "passive"))
    )
    (net (code "61") (name "RC5") (class "Default")
      (node (ref "IC1") (pin "38") (pinfunction "RP21/CN26/PMA3/RC5_38") (pintype "bidirectional"))
    )
    (net (code "62") (name "RC8") (class "Default")
      (node (ref "IC1") (pin "4") (pinfunction "RP24/CN20/PMA5/RC8_4") (pintype "bidirectional"))
      (node (ref "U$10") (pin "16") (pinfunction "16_16") (pintype "passive"))
    )
    (net (code "63") (name "VPP") (class "Default")
      (node (ref "U$10") (pin "8") (pinfunction "8_8") (pintype "passive"))
      (node (ref "X2") (pin "4") (pinfunction "4_4") (pintype "passive"))
    )
    (net (code "64") (name "unconnected-(IC1-AN7{slash}RP17{slash}CN9{slash}RC1-Pad26)") (class "Default")
      (node (ref "IC1") (pin "26") (pinfunction "AN7/RP17/CN9/RC1_26") (pintype "bidirectional"))
    )
    (net (code "65") (name "unconnected-(IC1-AN8{slash}CVREF{slash}RP18{slash}PMA2{slash}CN10{slash}RC2-Pad27)") (class "Default")
      (node (ref "IC1") (pin "27") (pinfunction "AN8/CVREF/RP18/PMA2/CN10/RC2_27") (pintype "bidirectional"))
    )
    (net (code "66") (name "unconnected-(IC1-RP25{slash}CN19{slash}PMA6{slash}RC9-Pad5)") (class "Default")
      (node (ref "IC1") (pin "5") (pinfunction "RP25/CN19/PMA6/RC9_5") (pintype "bidirectional"))
    )
    (net (code "67") (name "unconnected-(IC1-TDO{slash}PMA8{slash}RA8-Pad32)") (class "Default")
      (node (ref "IC1") (pin "32") (pinfunction "TDO/PMA8/RA8_32") (pintype "bidirectional"))
    )
    (net (code "68") (name "unconnected-(IC_L_HIGH-Pad1)") (class "Default")
      (node (ref "IC_L_HIGH") (pin "1") (pinfunction "1_1") (pintype "bidirectional"))
    )
    (net (code "69") (name "unconnected-(IC_L_LOW-Pad1)") (class "Default")
      (node (ref "IC_L_LOW") (pin "1") (pinfunction "1_1") (pintype "bidirectional"))
    )
    (net (code "70") (name "unconnected-(IC_R_HIGH-Pad1)") (class "Default")
      (node (ref "IC_R_HIGH") (pin "1") (pinfunction "1_1") (pintype "bidirectional"))
    )
    (net (code "71") (name "unconnected-(IC_R_LOW-Pad1)") (class "Default")
      (node (ref "IC_R_LOW") (pin "1") (pinfunction "1_1") (pintype "bidirectional"))
    )
    (net (code "72") (name "unconnected-(U$8-Pad1)") (class "Default")
      (node (ref "U$8") (pin "1") (pinfunction "1_1") (pintype "bidirectional"))
    )
    (net (code "73") (name "unconnected-(U$10-Pad1)") (class "Default")
      (node (ref "U$10") (pin "1") (pinfunction "1_1") (pintype "passive"))
    )
    (net (code "74") (name "unconnected-(U$10-Pad2)") (class "Default")
      (node (ref "U$10") (pin "2") (pinfunction "2_2") (pintype "passive"))
    )
    (net (code "75") (name "unconnected-(U$10-Pad3)") (class "Default")
      (node (ref "U$10") (pin "3") (pinfunction "3_3") (pintype "passive"))
    )
    (net (code "76") (name "unconnected-(U$10-Pad10)") (class "Default")
      (node (ref "U$10") (pin "10") (pinfunction "10_10") (pintype "passive"))
    )
    (net (code "77") (name "unconnected-(U$10-Pad11)") (class "Default")
      (node (ref "U$10") (pin "11") (pinfunction "11_11") (pintype "passive"))
    )
    (net (code "78") (name "unconnected-(U$10-Pad12)") (class "Default")
      (node (ref "U$10") (pin "12") (pinfunction "12_12") (pintype "passive"))
    )
    (net (code "79") (name "unconnected-(U$10-Pad13)") (class "Default")
      (node (ref "U$10") (pin "13") (pinfunction "13_13") (pintype "passive"))
    )
    (net (code "80") (name "unconnected-(U$69-P$1-Pad1)") (class "Default")
      (node (ref "U$69") (pin "1") (pinfunction "P$1_1") (pintype "bidirectional"))
    )
    (net (code "81") (name "unconnected-(U$69-P$2-Pad2)") (class "Default")
      (node (ref "U$69") (pin "2") (pinfunction "P$2_2") (pintype "bidirectional"))
    )
    (net (code "82") (name "unconnected-(U$69-P$4-Pad4)") (class "Default")
      (node (ref "U$69") (pin "4") (pinfunction "P$4_4") (pintype "bidirectional"))
    )
    (net (code "83") (name "unconnected-(U$82-VREF-Pad5)") (class "Default")
      (node (ref "U$82") (pin "5") (pinfunction "VREF_5") (pintype "bidirectional"))
    )
  )
)
